# IO_Shield_With_Power_Supply.net
KiCad netlist of a schematic drawn in EAGLE
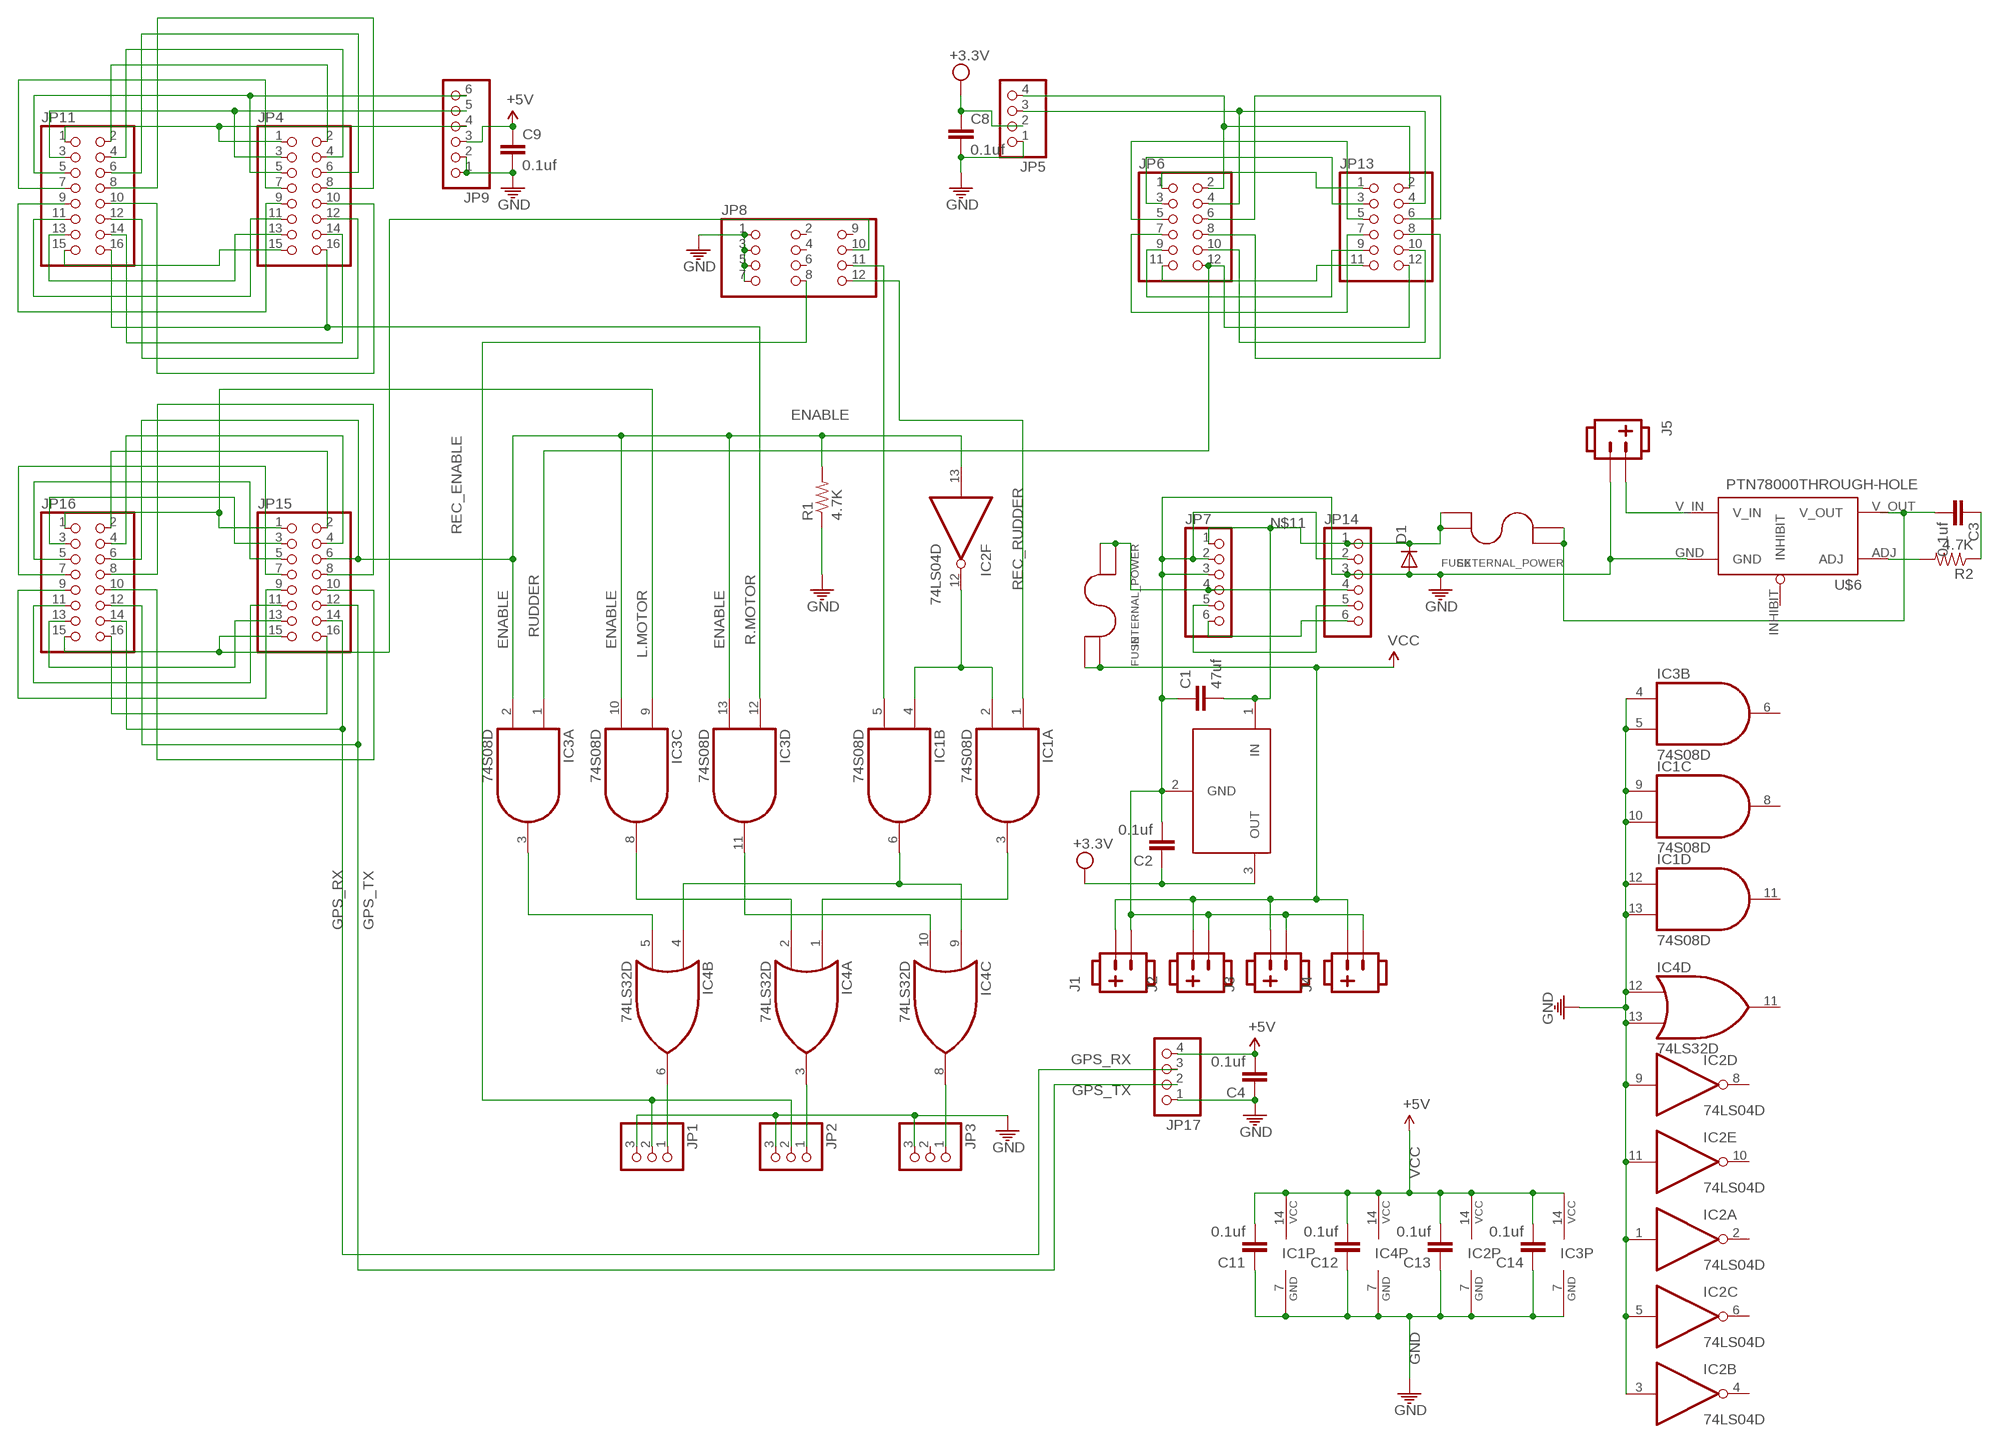
[diagram p0: schematic, sheet 1]

(export (version "E")
  (design (tool "Eeschema 10.0.6"))
  (components
    (comp (ref "C1")
      (value "47uf")
      (footprint "eagle-import:C0805")
      (libsource (lib "eagle-import") (part "C-EUC0805"))
    )
    (comp (ref "C2")
      (value "0.1uf")
      (footprint "eagle-import:C0805")
      (libsource (lib "eagle-import") (part "C-EUC0805"))
    )
    (comp (ref "C3")
      (value "0.1uf")
      (footprint "eagle-import:C0805")
      (libsource (lib "eagle-import") (part "C-EUC0805"))
    )
    (comp (ref "C4")
      (value "0.1uf")
      (footprint "eagle-import:C0805")
      (libsource (lib "eagle-import") (part "C-EUC0805"))
    )
    (comp (ref "C8")
      (value "0.1uf")
      (footprint "eagle-import:C0805")
      (libsource (lib "eagle-import") (part "C-EUC0805"))
    )
    (comp (ref "C9")
      (value "0.1uf")
      (footprint "eagle-import:C0805")
      (libsource (lib "eagle-import") (part "C-EUC0805"))
    )
    (comp (ref "C11")
      (value "0.1uf")
      (footprint "eagle-import:C0805")
      (libsource (lib "eagle-import") (part "C-EUC0805"))
    )
    (comp (ref "C12")
      (value "0.1uf")
      (footprint "eagle-import:C0805")
      (libsource (lib "eagle-import") (part "C-EUC0805"))
    )
    (comp (ref "C13")
      (value "0.1uf")
      (footprint "eagle-import:C0805")
      (libsource (lib "eagle-import") (part "C-EUC0805"))
    )
    (comp (ref "C14")
      (value "0.1uf")
      (footprint "eagle-import:C0805")
      (libsource (lib "eagle-import") (part "C-EUC0805"))
    )
    (comp (ref "D1")
      (value "DIODEPTH")
      (footprint "eagle-import:DIODE-1N4001")
      (libsource (lib "eagle-import") (part "DIODEPTH"))
    )
    (comp (ref "EXTERNAL_POWER")
      (value "FUSE")
      (footprint "eagle-import:FUSE_2AG")
      (libsource (lib "eagle-import") (part "FUSE"))
    )
    (comp (ref "IC1")
      (value "74S08D")
      (footprint "eagle-import:SO14")
      (libsource (lib "eagle-import") (part "7408DS"))
    )
    (comp (ref "IC2")
      (value "74LS04D")
      (footprint "eagle-import:SO14")
      (libsource (lib "eagle-import") (part "7404DLS"))
    )
    (comp (ref "IC3")
      (value "74S08D")
      (footprint "eagle-import:SO14")
      (libsource (lib "eagle-import") (part "7408DS"))
    )
    (comp (ref "IC4")
      (value "74LS32D")
      (footprint "eagle-import:SO14")
      (libsource (lib "eagle-import") (part "7432DLS"))
    )
    (comp (ref "INTERNAL_POWER")
      (value "FUSE")
      (footprint "eagle-import:FUSE_2AG")
      (libsource (lib "eagle-import") (part "FUSE"))
    )
    (comp (ref "J1")
      (value "POW_CONNECTFEMALE-RA")
      (footprint "eagle-import:SOCKET-FEMALE_RA-3.96MM-2")
      (libsource (lib "eagle-import") (part "POW_CONNECTFEMALE-RA"))
    )
    (comp (ref "J2")
      (value "POW_CONNECTFEMALE-RA")
      (footprint "eagle-import:SOCKET-FEMALE_RA-3.96MM-2")
      (libsource (lib "eagle-import") (part "POW_CONNECTFEMALE-RA"))
    )
    (comp (ref "J3")
      (value "POW_CONNECTFEMALE-RA")
      (footprint "eagle-import:SOCKET-FEMALE_RA-3.96MM-2")
      (libsource (lib "eagle-import") (part "POW_CONNECTFEMALE-RA"))
    )
    (comp (ref "J4")
      (value "POW_CONNECTFEMALE-RA")
      (footprint "eagle-import:SOCKET-FEMALE_RA-3.96MM-2")
      (libsource (lib "eagle-import") (part "POW_CONNECTFEMALE-RA"))
    )
    (comp (ref "J5")
      (value "POW_CONNECTFEMALE-RA")
      (footprint "eagle-import:SOCKET-FEMALE_RA-3.96MM-2")
      (libsource (lib "eagle-import") (part "POW_CONNECTFEMALE-RA"))
    )
    (comp (ref "JP1")
      (value "PINHD-1X3/90")
      (footprint "eagle-import:1X03_90")
      (libsource (lib "eagle-import") (part "PINHD-1X3/90"))
    )
    (comp (ref "JP2")
      (value "PINHD-1X3/90")
      (footprint "eagle-import:1X03_90")
      (libsource (lib "eagle-import") (part "PINHD-1X3/90"))
    )
    (comp (ref "JP3")
      (value "PINHD-1X3/90")
      (footprint "eagle-import:1X03_90")
      (libsource (lib "eagle-import") (part "PINHD-1X3/90"))
    )
    (comp (ref "JP4")
      (value "PINHD-2X8")
      (footprint "eagle-import:2X08")
      (libsource (lib "eagle-import") (part "PINHD-2X8"))
    )
    (comp (ref "JP5")
      (value "PINHD-1X4")
      (footprint "eagle-import:1X04")
      (libsource (lib "eagle-import") (part "PINHD-1X4"))
    )
    (comp (ref "JP6")
      (value "PINHD-2X6")
      (footprint "eagle-import:2X06")
      (libsource (lib "eagle-import") (part "PINHD-2X6"))
    )
    (comp (ref "JP7")
      (value "PINHD-1X6")
      (footprint "eagle-import:1X06")
      (libsource (lib "eagle-import") (part "pinhead_PINHD-1X6"))
    )
    (comp (ref "JP8")
      (value "PINHD-2X4")
      (footprint "eagle-import:2X04")
      (libsource (lib "eagle-import") (part "PINHD-2X4"))
    )
    (comp (ref "JP9")
      (value "PINHD-1X6")
      (footprint "eagle-import:1X06")
      (libsource (lib "eagle-import") (part "PINHD-1X6"))
    )
    (comp (ref "JP11")
      (value "PINHD-2X8")
      (footprint "eagle-import:2X08")
      (libsource (lib "eagle-import") (part "PINHD-2X8"))
    )
    (comp (ref "JP13")
      (value "PINHD-2X6")
      (footprint "eagle-import:2X06")
      (libsource (lib "eagle-import") (part "PINHD-2X6"))
    )
    (comp (ref "JP14")
      (value "PINHD-1X6")
      (footprint "eagle-import:1X06")
      (libsource (lib "eagle-import") (part "pinhead_PINHD-1X6"))
    )
    (comp (ref "JP15")
      (value "PINHD-2X8")
      (footprint "eagle-import:2X08")
      (libsource (lib "eagle-import") (part "PINHD-2X8"))
    )
    (comp (ref "JP16")
      (value "PINHD-2X8")
      (footprint "eagle-import:2X08")
      (libsource (lib "eagle-import") (part "PINHD-2X8"))
    )
    (comp (ref "JP17")
      (value "PINHD-1X4")
      (footprint "eagle-import:1X04")
      (libsource (lib "eagle-import") (part "pinhead_PINHD-1X4"))
    )
    (comp (ref "R1")
      (value "4.7K")
      (footprint "eagle-import:0805")
      (libsource (lib "eagle-import") (part "RESISTOR0805-RES"))
    )
    (comp (ref "R2")
      (value "4.7K")
      (footprint "eagle-import:0805")
      (libsource (lib "eagle-import") (part "RESISTOR0805-RES"))
    )
    (comp (ref "U$1")
      (value "LM3940IMP-3.3")
      (footprint "eagle-import:SOT223")
      (libsource (lib "eagle-import") (part "LM3940IMP-3.3"))
    )
    (comp (ref "U$6")
      (value "PTN78000THROUGH-HOLE")
      (footprint "eagle-import:PTN78000")
      (libsource (lib "eagle-import") (part "PTN78000THROUGH-HOLE"))
    )
  )
  (nets
    (net (code "1") (name "+3.3V") (class "Default")
      (node (ref "C2") (pin "1") (pinfunction "1_1") (pintype "passive"))
      (node (ref "C8") (pin "1") (pinfunction "1_1") (pintype "passive"))
      (node (ref "JP5") (pin "2") (pinfunction "2_2") (pintype "passive"))
      (node (ref "U$1") (pin "3") (pinfunction "OUT_3") (pintype "power_in"))
    )
    (net (code "2") (name "+5V") (class "Default")
      (node (ref "C11") (pin "2") (pinfunction "2_2") (pintype "passive"))
      (node (ref "C12") (pin "2") (pinfunction "2_2") (pintype "passive"))
      (node (ref "C13") (pin "2") (pinfunction "2_2") (pintype "passive"))
      (node (ref "C14") (pin "2") (pinfunction "2_2") (pintype "passive"))
      (node (ref "C4") (pin "2") (pinfunction "2_2") (pintype "passive"))
      (node (ref "C9") (pin "1") (pinfunction "1_1") (pintype "passive"))
      (node (ref "IC1") (pin "14") (pinfunction "VCC_14") (pintype "power_in"))
      (node (ref "IC2") (pin "14") (pinfunction "VCC_14") (pintype "power_in"))
      (node (ref "IC3") (pin "14") (pinfunction "VCC_14") (pintype "power_in"))
      (node (ref "IC4") (pin "14") (pinfunction "VCC_14") (pintype "power_in"))
      (node (ref "INTERNAL_POWER") (pin "P$3") (pinfunction "3_P$3") (pintype "bidirectional"))
      (node (ref "INTERNAL_POWER") (pin "P$4") (pinfunction "4_P$4") (pintype "bidirectional"))
      (node (ref "J1") (pin "1") (pinfunction "1_1") (pintype "passive"))
      (node (ref "J2") (pin "1") (pinfunction "1_1") (pintype "passive"))
      (node (ref "J3") (pin "1") (pinfunction "1_1") (pintype "passive"))
      (node (ref "J4") (pin "1") (pinfunction "1_1") (pintype "passive"))
      (node (ref "JP17") (pin "4") (pinfunction "4_4") (pintype "passive"))
      (node (ref "JP9") (pin "3") (pinfunction "3_3") (pintype "passive"))
    )
    (net (code "3") (name "/ENABLE") (class "Default")
      (node (ref "IC2") (pin "13") (pinfunction "I_13") (pintype "input"))
      (node (ref "IC3") (pin "10") (pinfunction "I1_10") (pintype "input"))
      (node (ref "IC3") (pin "13") (pinfunction "I1_13") (pintype "input"))
      (node (ref "IC3") (pin "2") (pinfunction "I1_2") (pintype "input"))
      (node (ref "JP15") (pin "6") (pinfunction "6_6") (pintype "passive"))
      (node (ref "JP16") (pin "6") (pinfunction "6_6") (pintype "passive"))
      (node (ref "R1") (pin "2") (pinfunction "2_2") (pintype "passive"))
    )
    (net (code "4") (name "/GPS_RX") (class "Default")
      (node (ref "JP15") (pin "14") (pinfunction "14_14") (pintype "passive"))
      (node (ref "JP16") (pin "14") (pinfunction "14_14") (pintype "passive"))
      (node (ref "JP17") (pin "3") (pinfunction "3_3") (pintype "passive"))
    )
    (net (code "5") (name "/GPS_TX") (class "Default")
      (node (ref "JP15") (pin "12") (pinfunction "12_12") (pintype "passive"))
      (node (ref "JP16") (pin "12") (pinfunction "12_12") (pintype "passive"))
      (node (ref "JP17") (pin "2") (pinfunction "2_2") (pintype "passive"))
    )
    (net (code "6") (name "/L.MOTOR") (class "Default")
      (node (ref "IC3") (pin "9") (pinfunction "I0_9") (pintype "input"))
      (node (ref "JP15") (pin "1") (pinfunction "1_1") (pintype "passive"))
      (node (ref "JP16") (pin "1") (pinfunction "1_1") (pintype "passive"))
    )
    (net (code "7") (name "/N$11") (class "Default")
      (node (ref "C1") (pin "2") (pinfunction "2_2") (pintype "passive"))
      (node (ref "D1") (pin "C") (pinfunction "C_C") (pintype "passive"))
      (node (ref "EXTERNAL_POWER") (pin "P$3") (pinfunction "3_P$3") (pintype "bidirectional"))
      (node (ref "EXTERNAL_POWER") (pin "P$4") (pinfunction "4_P$4") (pintype "bidirectional"))
      (node (ref "JP14") (pin "1") (pinfunction "1_1") (pintype "passive"))
      (node (ref "JP7") (pin "1") (pinfunction "1_1") (pintype "passive"))
      (node (ref "U$1") (pin "1") (pinfunction "IN_1") (pintype "power_in"))
    )
    (net (code "8") (name "/R.MOTOR") (class "Default")
      (node (ref "IC3") (pin "12") (pinfunction "I0_12") (pintype "input"))
      (node (ref "JP11") (pin "16") (pinfunction "16_16") (pintype "passive"))
      (node (ref "JP4") (pin "16") (pinfunction "16_16") (pintype "passive"))
    )
    (net (code "9") (name "/REC_ENABLE") (class "Default")
      (node (ref "JP15") (pin "16") (pinfunction "16_16") (pintype "passive"))
      (node (ref "JP16") (pin "16") (pinfunction "16_16") (pintype "passive"))
    )
    (net (code "10") (name "/REC_RUDDER") (class "Default")
      (node (ref "IC1") (pin "1") (pinfunction "I0_1") (pintype "input"))
      (node (ref "JP8") (pin "12") (pinfunction "12_12") (pintype "passive"))
    )
    (net (code "11") (name "/RUDDER") (class "Default")
      (node (ref "IC3") (pin "1") (pinfunction "I0_1") (pintype "input"))
      (node (ref "JP13") (pin "12") (pinfunction "12_12") (pintype "passive"))
      (node (ref "JP6") (pin "12") (pinfunction "12_12") (pintype "passive"))
    )
    (net (code "12") (name "GND") (class "Default")
      (node (ref "C1") (pin "1") (pinfunction "1_1") (pintype "passive"))
      (node (ref "C11") (pin "1") (pinfunction "1_1") (pintype "passive"))
      (node (ref "C12") (pin "1") (pinfunction "1_1") (pintype "passive"))
      (node (ref "C13") (pin "1") (pinfunction "1_1") (pintype "passive"))
      (node (ref "C14") (pin "1") (pinfunction "1_1") (pintype "passive"))
      (node (ref "C2") (pin "2") (pinfunction "2_2") (pintype "passive"))
      (node (ref "C4") (pin "1") (pinfunction "1_1") (pintype "passive"))
      (node (ref "C8") (pin "2") (pinfunction "2_2") (pintype "passive"))
      (node (ref "C9") (pin "2") (pinfunction "2_2") (pintype "passive"))
      (node (ref "D1") (pin "A") (pinfunction "A_A") (pintype "passive"))
      (node (ref "IC1") (pin "10") (pinfunction "I1_10") (pintype "input"))
      (node (ref "IC1") (pin "12") (pinfunction "I0_12") (pintype "input"))
      (node (ref "IC1") (pin "13") (pinfunction "I1_13") (pintype "input"))
      (node (ref "IC1") (pin "7") (pinfunction "GND_7") (pintype "power_in"))
      (node (ref "IC1") (pin "9") (pinfunction "I0_9") (pintype "input"))
      (node (ref "IC2") (pin "1") (pinfunction "I_1") (pintype "input"))
      (node (ref "IC2") (pin "11") (pinfunction "I_11") (pintype "input"))
      (node (ref "IC2") (pin "3") (pinfunction "I_3") (pintype "input"))
      (node (ref "IC2") (pin "5") (pinfunction "I_5") (pintype "input"))
      (node (ref "IC2") (pin "7") (pinfunction "GND_7") (pintype "power_in"))
      (node (ref "IC2") (pin "9") (pinfunction "I_9") (pintype "input"))
      (node (ref "IC3") (pin "4") (pinfunction "I0_4") (pintype "input"))
      (node (ref "IC3") (pin "5") (pinfunction "I1_5") (pintype "input"))
      (node (ref "IC3") (pin "7") (pinfunction "GND_7") (pintype "power_in"))
      (node (ref "IC4") (pin "12") (pinfunction "I0_12") (pintype "input"))
      (node (ref "IC4") (pin "13") (pinfunction "I1_13") (pintype "input"))
      (node (ref "IC4") (pin "7") (pinfunction "GND_7") (pintype "power_in"))
      (node (ref "J1") (pin "2") (pinfunction "2_2") (pintype "passive"))
      (node (ref "J2") (pin "2") (pinfunction "2_2") (pintype "passive"))
      (node (ref "J3") (pin "2") (pinfunction "2_2") (pintype "passive"))
      (node (ref "J4") (pin "2") (pinfunction "2_2") (pintype "passive"))
      (node (ref "J5") (pin "2") (pinfunction "2_2") (pintype "passive"))
      (node (ref "JP1") (pin "3") (pinfunction "3_3") (pintype "passive"))
      (node (ref "JP14") (pin "2") (pinfunction "2_2") (pintype "passive"))
      (node (ref "JP14") (pin "3") (pinfunction "3_3") (pintype "passive"))
      (node (ref "JP17") (pin "1") (pinfunction "1_1") (pintype "passive"))
      (node (ref "JP2") (pin "3") (pinfunction "3_3") (pintype "passive"))
      (node (ref "JP3") (pin "3") (pinfunction "3_3") (pintype "passive"))
      (node (ref "JP5") (pin "1") (pinfunction "1_1") (pintype "passive"))
      (node (ref "JP7") (pin "2") (pinfunction "2_2") (pintype "passive"))
      (node (ref "JP7") (pin "3") (pinfunction "3_3") (pintype "passive"))
      (node (ref "JP8") (pin "1") (pinfunction "1_1") (pintype "passive"))
      (node (ref "JP8") (pin "3") (pinfunction "3_3") (pintype "passive"))
      (node (ref "JP8") (pin "5") (pinfunction "5_5") (pintype "passive"))
      (node (ref "JP8") (pin "7") (pinfunction "7_7") (pintype "passive"))
      (node (ref "JP9") (pin "1") (pinfunction "1_1") (pintype "passive"))
      (node (ref "JP9") (pin "2") (pinfunction "2_2") (pintype "passive"))
      (node (ref "R1") (pin "1") (pinfunction "1_1") (pintype "passive"))
      (node (ref "U$1") (pin "2") (pinfunction "GND_2") (pintype "power_in"))
      (node (ref "U$6") (pin "GND") (pinfunction "GND_GND") (pintype "power_in"))
    )
    (net (code "13") (name "Net-(C3-Pad1)") (class "Default")
      (node (ref "C3") (pin "1") (pinfunction "1_1") (pintype "passive"))
      (node (ref "R2") (pin "1") (pinfunction "1_1") (pintype "passive"))
    )
    (net (code "14") (name "Net-(EXTERNAL_POWER-1)") (class "Default")
      (node (ref "C3") (pin "2") (pinfunction "2_2") (pintype "passive"))
      (node (ref "EXTERNAL_POWER") (pin "P$1") (pinfunction "1_P$1") (pintype "bidirectional"))
      (node (ref "EXTERNAL_POWER") (pin "P$2") (pinfunction "2_P$2") (pintype "bidirectional"))
      (node (ref "U$6") (pin "V_OUT") (pinfunction "V_OUT_V_OUT") (pintype "output"))
    )
    (net (code "15") (name "Net-(IC1A-I1)") (class "Default")
      (node (ref "IC1") (pin "2") (pinfunction "I1_2") (pintype "input"))
      (node (ref "IC1") (pin "4") (pinfunction "I0_4") (pintype "input"))
      (node (ref "IC2") (pin "12") (pinfunction "O_12") (pintype "output"))
    )
    (net (code "16") (name "Net-(IC1A-O)") (class "Default")
      (node (ref "IC1") (pin "3") (pinfunction "O_3") (pintype "output"))
      (node (ref "IC4") (pin "1") (pinfunction "I0_1") (pintype "input"))
    )
    (net (code "17") (name "Net-(IC1B-I1)") (class "Default")
      (node (ref "IC1") (pin "5") (pinfunction "I1_5") (pintype "input"))
      (node (ref "JP8") (pin "11") (pinfunction "11_11") (pintype "passive"))
    )
    (net (code "18") (name "Net-(IC1B-O)") (class "Default")
      (node (ref "IC1") (pin "6") (pinfunction "O_6") (pintype "output"))
      (node (ref "IC4") (pin "4") (pinfunction "I0_4") (pintype "input"))
      (node (ref "IC4") (pin "9") (pinfunction "I0_9") (pintype "input"))
    )
    (net (code "19") (name "Net-(IC3A-O)") (class "Default")
      (node (ref "IC3") (pin "3") (pinfunction "O_3") (pintype "output"))
      (node (ref "IC4") (pin "5") (pinfunction "I1_5") (pintype "input"))
    )
    (net (code "20") (name "Net-(IC3C-O)") (class "Default")
      (node (ref "IC3") (pin "8") (pinfunction "O_8") (pintype "output"))
      (node (ref "IC4") (pin "2") (pinfunction "I1_2") (pintype "input"))
    )
    (net (code "21") (name "Net-(IC3D-O)") (class "Default")
      (node (ref "IC3") (pin "11") (pinfunction "O_11") (pintype "output"))
      (node (ref "IC4") (pin "10") (pinfunction "I1_10") (pintype "input"))
    )
    (net (code "22") (name "Net-(IC4A-O)") (class "Default")
      (node (ref "IC4") (pin "3") (pinfunction "O_3") (pintype "output"))
      (node (ref "JP2") (pin "1") (pinfunction "1_1") (pintype "passive"))
    )
    (net (code "23") (name "Net-(IC4B-O)") (class "Default")
      (node (ref "IC4") (pin "6") (pinfunction "O_6") (pintype "output"))
      (node (ref "JP1") (pin "1") (pinfunction "1_1") (pintype "passive"))
    )
    (net (code "24") (name "Net-(IC4C-O)") (class "Default")
      (node (ref "IC4") (pin "8") (pinfunction "O_8") (pintype "output"))
      (node (ref "JP3") (pin "1") (pinfunction "1_1") (pintype "passive"))
    )
    (net (code "25") (name "Net-(INTERNAL_POWER-1)") (class "Default")
      (node (ref "INTERNAL_POWER") (pin "P$1") (pinfunction "1_P$1") (pintype "bidirectional"))
      (node (ref "INTERNAL_POWER") (pin "P$2") (pinfunction "2_P$2") (pintype "bidirectional"))
      (node (ref "JP14") (pin "4") (pinfunction "4_4") (pintype "passive"))
      (node (ref "JP7") (pin "4") (pinfunction "4_4") (pintype "passive"))
    )
    (net (code "26") (name "Net-(J5-Pad1)") (class "Default")
      (node (ref "J5") (pin "1") (pinfunction "1_1") (pintype "passive"))
      (node (ref "U$6") (pin "V_IN") (pinfunction "V_IN_V_IN") (pintype "power_in"))
    )
    (net (code "27") (name "Net-(JP1-Pad2)") (class "Default")
      (node (ref "JP1") (pin "2") (pinfunction "2_2") (pintype "passive"))
      (node (ref "JP2") (pin "2") (pinfunction "2_2") (pintype "passive"))
      (node (ref "JP8") (pin "8") (pinfunction "8_8") (pintype "passive"))
    )
    (net (code "28") (name "Net-(JP8-9)") (class "Default")
      (node (ref "JP15") (pin "15") (pinfunction "15_15") (pintype "passive"))
      (node (ref "JP16") (pin "15") (pinfunction "15_15") (pintype "passive"))
      (node (ref "JP8") (pin "10") (pinfunction "9_10") (pintype "passive"))
    )
    (net (code "29") (name "Net-(JP11-Pad1)") (class "Default")
      (node (ref "JP11") (pin "1") (pinfunction "1_1") (pintype "passive"))
      (node (ref "JP4") (pin "1") (pinfunction "1_1") (pintype "passive"))
      (node (ref "JP9") (pin "4") (pinfunction "4_4") (pintype "passive"))
    )
    (net (code "30") (name "Net-(JP11-Pad2)") (class "Default")
      (node (ref "JP11") (pin "2") (pinfunction "2_2") (pintype "passive"))
      (node (ref "JP4") (pin "2") (pinfunction "2_2") (pintype "passive"))
    )
    (net (code "31") (name "Net-(JP11-Pad3)") (class "Default")
      (node (ref "JP11") (pin "3") (pinfunction "3_3") (pintype "passive"))
      (node (ref "JP4") (pin "3") (pinfunction "3_3") (pintype "passive"))
      (node (ref "JP9") (pin "5") (pinfunction "5_5") (pintype "passive"))
    )
    (net (code "32") (name "Net-(JP11-Pad4)") (class "Default")
      (node (ref "JP11") (pin "4") (pinfunction "4_4") (pintype "passive"))
      (node (ref "JP4") (pin "4") (pinfunction "4_4") (pintype "passive"))
    )
    (net (code "33") (name "Net-(JP11-Pad5)") (class "Default")
      (node (ref "JP11") (pin "5") (pinfunction "5_5") (pintype "passive"))
      (node (ref "JP4") (pin "5") (pinfunction "5_5") (pintype "passive"))
      (node (ref "JP9") (pin "6") (pinfunction "6_6") (pintype "passive"))
    )
    (net (code "34") (name "Net-(JP11-Pad6)") (class "Default")
      (node (ref "JP11") (pin "6") (pinfunction "6_6") (pintype "passive"))
      (node (ref "JP4") (pin "6") (pinfunction "6_6") (pintype "passive"))
    )
    (net (code "35") (name "Net-(JP11-Pad7)") (class "Default")
      (node (ref "JP11") (pin "7") (pinfunction "7_7") (pintype "passive"))
      (node (ref "JP4") (pin "7") (pinfunction "7_7") (pintype "passive"))
    )
    (net (code "36") (name "Net-(JP11-Pad8)") (class "Default")
      (node (ref "JP11") (pin "8") (pinfunction "8_8") (pintype "passive"))
      (node (ref "JP4") (pin "8") (pinfunction "8_8") (pintype "passive"))
    )
    (net (code "37") (name "Net-(JP11-Pad9)") (class "Default")
      (node (ref "JP11") (pin "9") (pinfunction "9_9") (pintype "passive"))
      (node (ref "JP4") (pin "9") (pinfunction "9_9") (pintype "passive"))
    )
    (net (code "38") (name "Net-(JP11-Pad10)") (class "Default")
      (node (ref "JP11") (pin "10") (pinfunction "10_10") (pintype "passive"))
      (node (ref "JP4") (pin "10") (pinfunction "10_10") (pintype "passive"))
    )
    (net (code "39") (name "Net-(JP11-Pad11)") (class "Default")
      (node (ref "JP11") (pin "11") (pinfunction "11_11") (pintype "passive"))
      (node (ref "JP4") (pin "11") (pinfunction "11_11") (pintype "passive"))
    )
    (net (code "40") (name "Net-(JP11-Pad12)") (class "Default")
      (node (ref "JP11") (pin "12") (pinfunction "12_12") (pintype "passive"))
      (node (ref "JP4") (pin "12") (pinfunction "12_12") (pintype "passive"))
    )
    (net (code "41") (name "Net-(JP11-Pad13)") (class "Default")
      (node (ref "JP11") (pin "13") (pinfunction "13_13") (pintype "passive"))
      (node (ref "JP4") (pin "13") (pinfunction "13_13") (pintype "passive"))
    )
    (net (code "42") (name "Net-(JP11-Pad14)") (class "Default")
      (node (ref "JP11") (pin "14") (pinfunction "14_14") (pintype "passive"))
      (node (ref "JP4") (pin "14") (pinfunction "14_14") (pintype "passive"))
    )
    (net (code "43") (name "Net-(JP11-Pad15)") (class "Default")
      (node (ref "JP11") (pin "15") (pinfunction "15_15") (pintype "passive"))
      (node (ref "JP4") (pin "15") (pinfunction "15_15") (pintype "passive"))
    )
    (net (code "44") (name "Net-(JP13-Pad1)") (class "Default")
      (node (ref "JP13") (pin "1") (pinfunction "1_1") (pintype "passive"))
      (node (ref "JP6") (pin "1") (pinfunction "1_1") (pintype "passive"))
    )
    (net (code "45") (name "Net-(JP13-Pad2)") (class "Default")
      (node (ref "JP13") (pin "2") (pinfunction "2_2") (pintype "passive"))
      (node (ref "JP5") (pin "4") (pinfunction "4_4") (pintype "passive"))
      (node (ref "JP6") (pin "2") (pinfunction "2_2") (pintype "passive"))
    )
    (net (code "46") (name "Net-(JP13-Pad3)") (class "Default")
      (node (ref "JP13") (pin "3") (pinfunction "3_3") (pintype "passive"))
      (node (ref "JP6") (pin "3") (pinfunction "3_3") (pintype "passive"))
    )
    (net (code "47") (name "Net-(JP13-Pad4)") (class "Default")
      (node (ref "JP13") (pin "4") (pinfunction "4_4") (pintype "passive"))
      (node (ref "JP5") (pin "3") (pinfunction "3_3") (pintype "passive"))
      (node (ref "JP6") (pin "4") (pinfunction "4_4") (pintype "passive"))
    )
    (net (code "48") (name "Net-(JP13-Pad5)") (class "Default")
      (node (ref "JP13") (pin "5") (pinfunction "5_5") (pintype "passive"))
      (node (ref "JP6") (pin "5") (pinfunction "5_5") (pintype "passive"))
    )
    (net (code "49") (name "Net-(JP13-Pad6)") (class "Default")
      (node (ref "JP13") (pin "6") (pinfunction "6_6") (pintype "passive"))
      (node (ref "JP6") (pin "6") (pinfunction "6_6") (pintype "passive"))
    )
    (net (code "50") (name "Net-(JP13-Pad7)") (class "Default")
      (node (ref "JP13") (pin "7") (pinfunction "7_7") (pintype "passive"))
      (node (ref "JP6") (pin "7") (pinfunction "7_7") (pintype "passive"))
    )
    (net (code "51") (name "Net-(JP13-Pad8)") (class "Default")
      (node (ref "JP13") (pin "8") (pinfunction "8_8") (pintype "passive"))
      (node (ref "JP6") (pin "8") (pinfunction "8_8") (pintype "passive"))
    )
    (net (code "52") (name "Net-(JP13-Pad9)") (class "Default")
      (node (ref "JP13") (pin "9") (pinfunction "9_9") (pintype "passive"))
      (node (ref "JP6") (pin "9") (pinfunction "9_9") (pintype "passive"))
    )
    (net (code "53") (name "Net-(JP13-Pad10)") (class "Default")
      (node (ref "JP13") (pin "10") (pinfunction "10_10") (pintype "passive"))
      (node (ref "JP6") (pin "10") (pinfunction "10_10") (pintype "passive"))
    )
    (net (code "54") (name "Net-(JP13-Pad11)") (class "Default")
      (node (ref "JP13") (pin "11") (pinfunction "11_11") (pintype "passive"))
      (node (ref "JP6") (pin "11") (pinfunction "11_11") (pintype "passive"))
    )
    (net (code "55") (name "Net-(JP14-Pad5)") (class "Default")
      (node (ref "JP14") (pin "5") (pinfunction "5_5") (pintype "passive"))
      (node (ref "JP7") (pin "5") (pinfunction "5_5") (pintype "passive"))
    )
    (net (code "56") (name "Net-(JP14-Pad6)") (class "Default")
      (node (ref "JP14") (pin "6") (pinfunction "6_6") (pintype "passive"))
      (node (ref "JP7") (pin "6") (pinfunction "6_6") (pintype "passive"))
    )
    (net (code "57") (name "Net-(JP15-Pad2)") (class "Default")
      (node (ref "JP15") (pin "2") (pinfunction "2_2") (pintype "passive"))
      (node (ref "JP16") (pin "2") (pinfunction "2_2") (pintype "passive"))
    )
    (net (code "58") (name "Net-(JP15-Pad3)") (class "Default")
      (node (ref "JP15") (pin "3") (pinfunction "3_3") (pintype "passive"))
      (node (ref "JP16") (pin "3") (pinfunction "3_3") (pintype "passive"))
    )
    (net (code "59") (name "Net-(JP15-Pad4)") (class "Default")
      (node (ref "JP15") (pin "4") (pinfunction "4_4") (pintype "passive"))
      (node (ref "JP16") (pin "4") (pinfunction "4_4") (pintype "passive"))
    )
    (net (code "60") (name "Net-(JP15-Pad5)") (class "Default")
      (node (ref "JP15") (pin "5") (pinfunction "5_5") (pintype "passive"))
      (node (ref "JP16") (pin "5") (pinfunction "5_5") (pintype "passive"))
    )
    (net (code "61") (name "Net-(JP15-Pad7)") (class "Default")
      (node (ref "JP15") (pin "7") (pinfunction "7_7") (pintype "passive"))
      (node (ref "JP16") (pin "7") (pinfunction "7_7") (pintype "passive"))
    )
    (net (code "62") (name "Net-(JP15-Pad8)") (class "Default")
      (node (ref "JP15") (pin "8") (pinfunction "8_8") (pintype "passive"))
      (node (ref "JP16") (pin "8") (pinfunction "8_8") (pintype "passive"))
    )
    (net (code "63") (name "Net-(JP15-Pad9)") (class "Default")
      (node (ref "JP15") (pin "9") (pinfunction "9_9") (pintype "passive"))
      (node (ref "JP16") (pin "9") (pinfunction "9_9") (pintype "passive"))
    )
    (net (code "64") (name "Net-(JP15-Pad10)") (class "Default")
      (node (ref "JP15") (pin "10") (pinfunction "10_10") (pintype "passive"))
      (node (ref "JP16") (pin "10") (pinfunction "10_10") (pintype "passive"))
    )
    (net (code "65") (name "Net-(JP15-Pad11)") (class "Default")
      (node (ref "JP15") (pin "11") (pinfunction "11_11") (pintype "passive"))
      (node (ref "JP16") (pin "11") (pinfunction "11_11") (pintype "passive"))
    )
    (net (code "66") (name "Net-(JP15-Pad13)") (class "Default")
      (node (ref "JP15") (pin "13") (pinfunction "13_13") (pintype "passive"))
      (node (ref "JP16") (pin "13") (pinfunction "13_13") (pintype "passive"))
    )
    (net (code "67") (name "Net-(R2-Pad2)") (class "Default")
      (node (ref "R2") (pin "2") (pinfunction "2_2") (pintype "passive"))
      (node (ref "U$6") (pin "ADJ") (pinfunction "ADJ_ADJ") (pintype "input"))
    )
    (net (code "68") (name "unconnected-(IC1C-O-Pad8)") (class "Default")
      (node (ref "IC1") (pin "8") (pinfunction "O_8") (pintype "output"))
    )
    (net (code "69") (name "unconnected-(IC1D-O-Pad11)") (class "Default")
      (node (ref "IC1") (pin "11") (pinfunction "O_11") (pintype "output"))
    )
    (net (code "70") (name "unconnected-(IC2A-O-Pad2)") (class "Default")
      (node (ref "IC2") (pin "2") (pinfunction "O_2") (pintype "output"))
    )
    (net (code "71") (name "unconnected-(IC2B-O-Pad4)") (class "Default")
      (node (ref "IC2") (pin "4") (pinfunction "O_4") (pintype "output"))
    )
    (net (code "72") (name "unconnected-(IC2C-O-Pad6)") (class "Default")
      (node (ref "IC2") (pin "6") (pinfunction "O_6") (pintype "output"))
    )
    (net (code "73") (name "unconnected-(IC2D-O-Pad8)") (class "Default")
      (node (ref "IC2") (pin "8") (pinfunction "O_8") (pintype "output"))
    )
    (net (code "74") (name "unconnected-(IC2E-O-Pad10)") (class "Default")
      (node (ref "IC2") (pin "10") (pinfunction "O_10") (pintype "output"))
    )
    (net (code "75") (name "unconnected-(IC3B-O-Pad6)") (class "Default")
      (node (ref "IC3") (pin "6") (pinfunction "O_6") (pintype "output"))
    )
    (net (code "76") (name "unconnected-(IC4D-O-Pad11)") (class "Default")
      (node (ref "IC4") (pin "11") (pinfunction "O_11") (pintype "output"))
    )
    (net (code "77") (name "unconnected-(JP3-Pad2)") (class "Default")
      (node (ref "JP3") (pin "2") (pinfunction "2_2") (pintype "passive"))
    )
    (net (code "78") (name "unconnected-(JP8-10-Pad9)") (class "Default")
      (node (ref "JP8") (pin "9") (pinfunction "10_9") (pintype "passive"))
    )
    (net (code "79") (name "unconnected-(JP8-Pad2)") (class "Default")
      (node (ref "JP8") (pin "2") (pinfunction "2_2") (pintype "passive"))
    )
    (net (code "80") (name "unconnected-(JP8-Pad4)") (class "Default")
      (node (ref "JP8") (pin "4") (pinfunction "4_4") (pintype "passive"))
    )
    (net (code "81") (name "unconnected-(JP8-Pad6)") (class "Default")
      (node (ref "JP8") (pin "6") (pinfunction "6_6") (pintype "passive"))
    )
    (net (code "82") (name "unconnected-(U$6-PadINHIBIT)") (class "Default")
      (node (ref "U$6") (pin "INHIBIT") (pinfunction "INHIBIT_INHIBIT") (pintype "input"))
    )
  )
)
